# RELAY8.net
KiCad netlist of a schematic drawn in Altium Designer
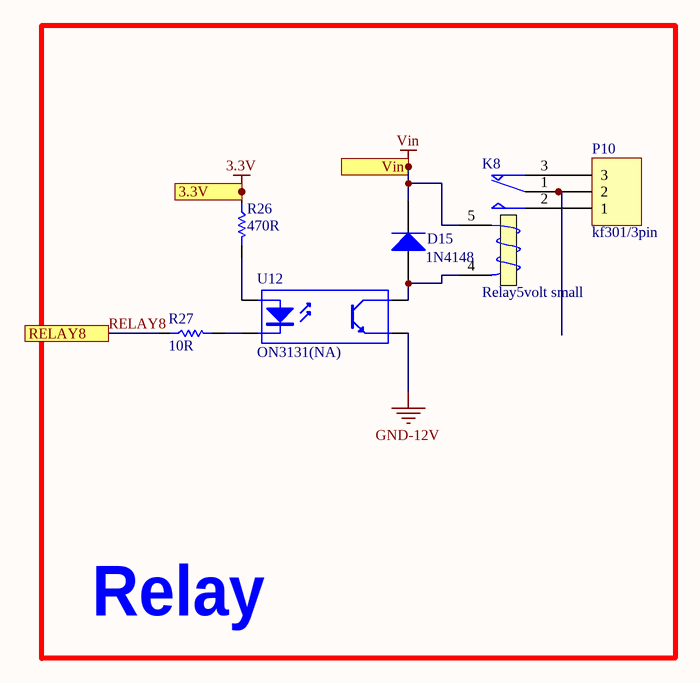
[diagram p0: RELAY8.SchDoc]

(export (version "E")
  (design (tool "Eeschema 10.0.6"))
  (components
    (comp (ref "D15")
      (value "1N4148")
      (footprint "sod123")
      (description "1 Amp General Purpose Rectifier")
      (fields (field (name "PUBLISHER") "Altium Limited"))
      (libsource (lib "Miscellaneous Devices") (part "Diode 1N4007"))
    )
    (comp (ref "K8")
      (value "Relay5volt small")
      (footprint "relay5_childern")
      (description "SPDT Relay")
      (fields (field (name "PUBLISHER") "Altium Limited"))
      (libsource (lib "FLIB") (part "Relay"))
    )
    (comp (ref "P10")
      (value "kf301/3pin")
      (footprint "Blue Connector 1*3 -kf301")
      (fields (field (name "PUBLISHER") "Altium Limited"))
      (libsource (lib "Miscellaneous Connectors") (part "Header 3"))
    )
    (comp (ref "R26")
      (value "470R")
      (footprint "0805/resistor")
      (description "Resistor")
      (fields (field (name "TOLERANCE") "5%") (field (name "POWER") "1/8 W"))
      (libsource (lib "skille") (part "Resistor"))
    )
    (comp (ref "R27")
      (value "10R")
      (footprint "0805/resistor")
      (description "Resistor")
      (fields (field (name "TOLERANCE") "5%") (field (name "POWER") "1/8 W"))
      (libsource (lib "skille") (part "Resistor"))
    )
    (comp (ref "U12")
      (value "ON3131(NA)")
      (footprint "OPTO_COUPLER")
      (description "4-Pin Phototransistor Optocoupler")
      (fields (field (name "PUBLISHER") "Altium Limited"))
      (libsource (lib "skille") (part "Optoisolator1"))
    )
  )
  (nets
    (net (code "1") (name "/RELAY8") (class "Default")
      (node (ref "R27") (pin "1") (pinfunction "1_1") (pintype "passive"))
    )
    (net (code "2") (name "3.3V") (class "Default")
      (node (ref "R26") (pin "1") (pinfunction "1_1") (pintype "passive"))
    )
    (net (code "3") (name "GND-12V") (class "Default")
      (node (ref "U12") (pin "3") (pinfunction "E_3") (pintype "passive"))
    )
    (net (code "4") (name "Net-(K8-COM)") (class "Default")
      (node (ref "K8") (pin "1") (pinfunction "COM_1") (pintype "passive"))
      (node (ref "P10") (pin "2") (pinfunction "2_2") (pintype "passive"))
    )
    (net (code "5") (name "Net-(K8-NO)") (class "Default")
      (node (ref "K8") (pin "2") (pinfunction "NO_2") (pintype "passive"))
      (node (ref "P10") (pin "1") (pinfunction "1_1") (pintype "passive"))
    )
    (net (code "6") (name "Net-(K8-T1)") (class "Default")
      (node (ref "K8") (pin "3") (pinfunction "T1_3") (pintype "passive"))
      (node (ref "P10") (pin "3") (pinfunction "3_3") (pintype "passive"))
    )
    (net (code "7") (name "Net-(K8-T2)") (class "Default")
      (node (ref "D15") (pin "A") (pinfunction "A_A") (pintype "passive"))
      (node (ref "K8") (pin "4") (pinfunction "T2_4") (pintype "passive"))
      (node (ref "U12") (pin "4") (pinfunction "C_4") (pintype "passive"))
    )
    (net (code "8") (name "Net-(U12-A)") (class "Default")
      (node (ref "R26") (pin "2") (pinfunction "2_2") (pintype "passive"))
      (node (ref "U12") (pin "1") (pinfunction "A_1") (pintype "passive"))
    )
    (net (code "9") (name "Net-(U12-K)") (class "Default")
      (node (ref "R27") (pin "2") (pinfunction "2_2") (pintype "passive"))
      (node (ref "U12") (pin "2") (pinfunction "K_2") (pintype "passive"))
    )
    (net (code "10") (name "Vin") (class "Default")
      (node (ref "D15") (pin "K") (pinfunction "K_K") (pintype "passive"))
      (node (ref "K8") (pin "5") (pinfunction "5_5") (pintype "passive"))
    )
  )
)
